# FrequencyGen.net
KiCad netlist of a schematic drawn in EAGLE
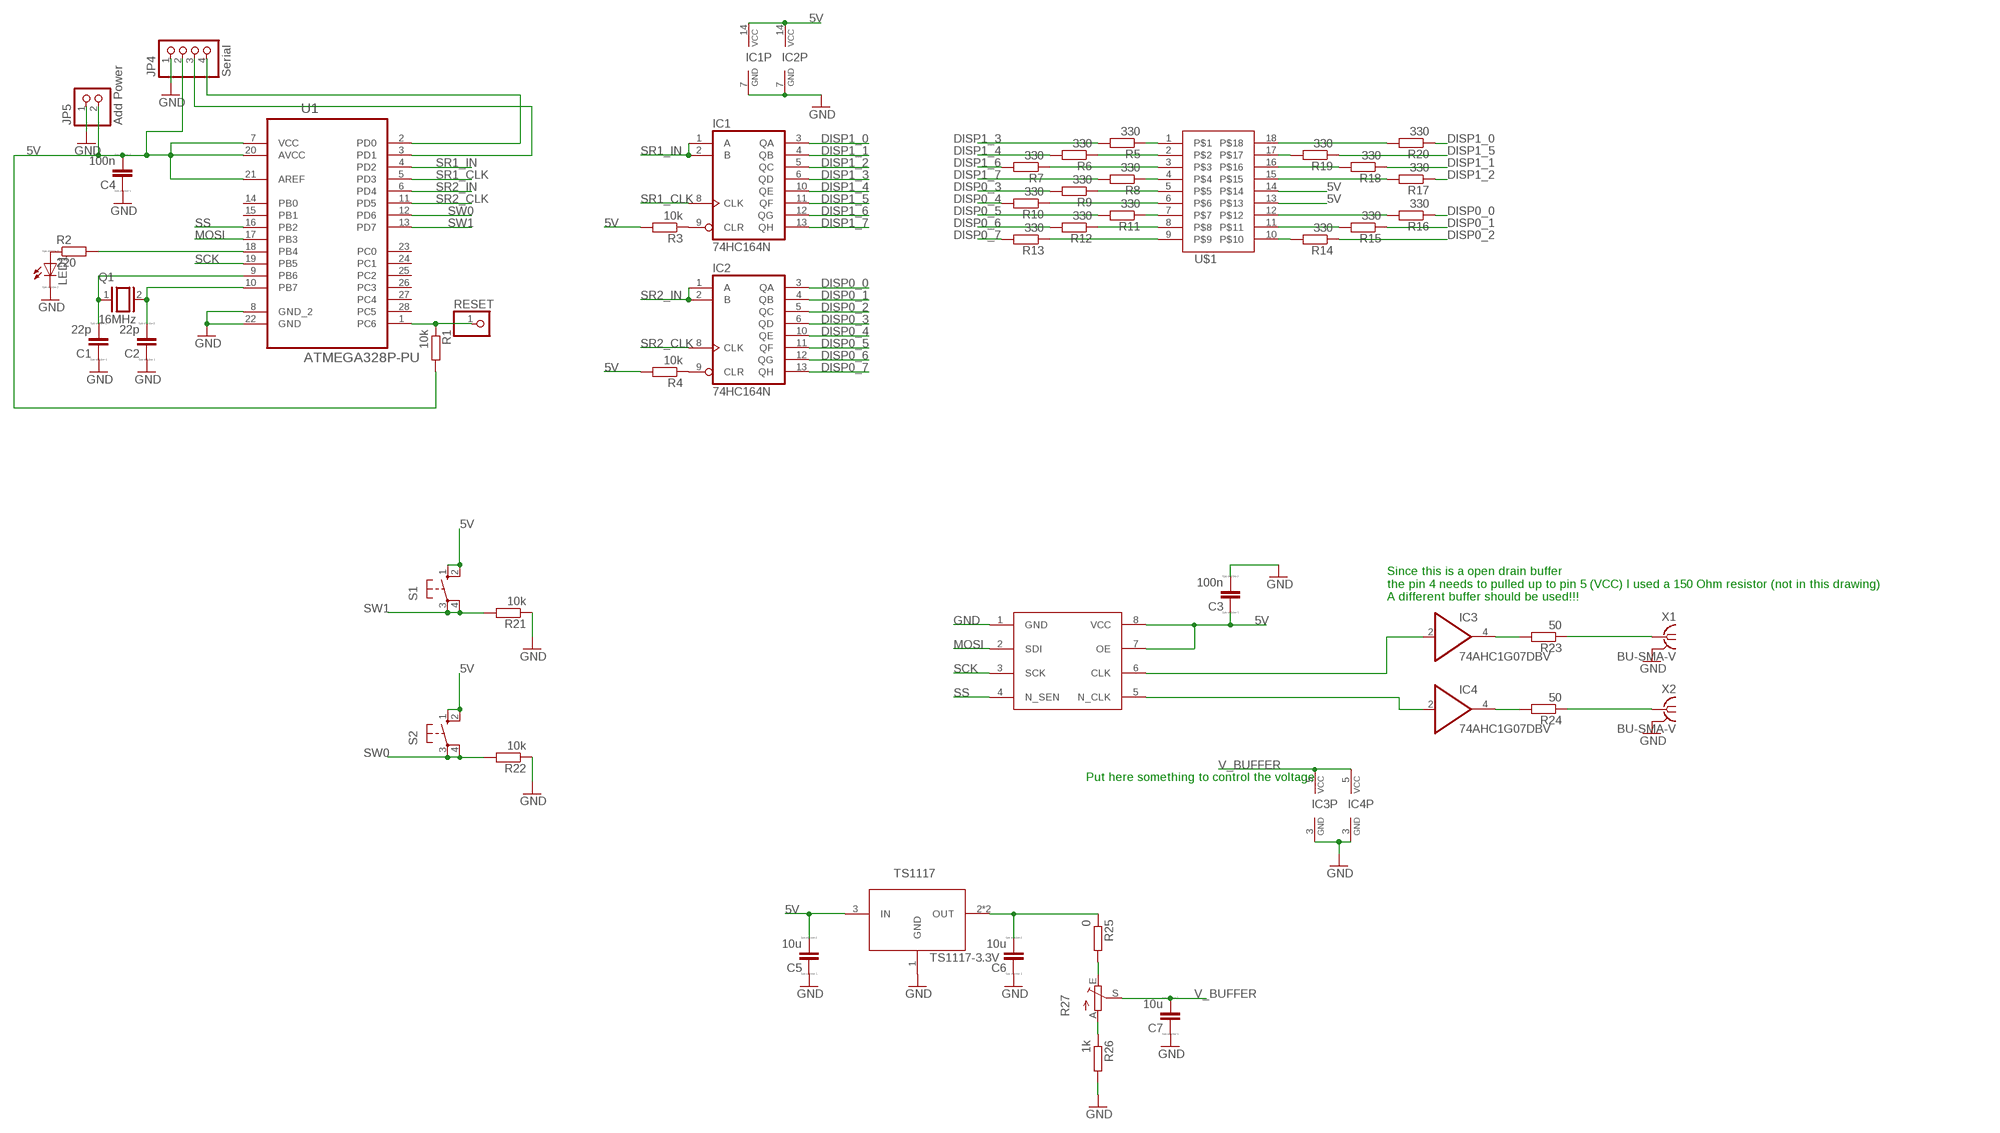
[diagram p0: schematic, sheet 1]

(export (version "E")
  (design (tool "Eeschema 10.0.6"))
  (components
    (comp (ref "C1")
      (value "22p")
      (footprint "eagle-import:C0805")
      (libsource (lib "eagle-import") (part "C_SMD"))
    )
    (comp (ref "C2")
      (value "22p")
      (footprint "eagle-import:C0805")
      (libsource (lib "eagle-import") (part "C_SMD"))
    )
    (comp (ref "C3")
      (value "100n")
      (footprint "eagle-import:C0805")
      (libsource (lib "eagle-import") (part "C_SMD"))
    )
    (comp (ref "C4")
      (value "100n")
      (footprint "eagle-import:C0805")
      (libsource (lib "eagle-import") (part "C_SMD"))
    )
    (comp (ref "C5")
      (value "10u")
      (footprint "eagle-import:C0805")
      (libsource (lib "eagle-import") (part "C_SMD"))
    )
    (comp (ref "C6")
      (value "10u")
      (footprint "eagle-import:C0805")
      (libsource (lib "eagle-import") (part "C_SMD"))
    )
    (comp (ref "C7")
      (value "10u")
      (footprint "eagle-import:C0805")
      (libsource (lib "eagle-import") (part "C_SMD"))
    )
    (comp (ref "IC1")
      (value "74HC164N")
      (footprint "eagle-import:DIL14")
      (libsource (lib "eagle-import") (part "74164NHC"))
    )
    (comp (ref "IC2")
      (value "74HC164N")
      (footprint "eagle-import:DIL14")
      (libsource (lib "eagle-import") (part "74164NHC"))
    )
    (comp (ref "IC3")
      (value "74AHC1G07DBV")
      (footprint "eagle-import:SOT23-5")
      (libsource (lib "eagle-import") (part "741G07DBVAHC"))
    )
    (comp (ref "IC4")
      (value "74AHC1G07DBV")
      (footprint "eagle-import:SOT23-5")
      (libsource (lib "eagle-import") (part "741G07DBVAHC"))
    )
    (comp (ref "JP4")
      (value "Serial")
      (footprint "eagle-import:1X04")
      (libsource (lib "eagle-import") (part "PINHD-1X4"))
    )
    (comp (ref "JP5")
      (value "Add Power")
      (footprint "eagle-import:1X02")
      (libsource (lib "eagle-import") (part "PINHD-1X2"))
    )
    (comp (ref "LED1")
      (value "LED_ELD260")
      (footprint "eagle-import:LED_LD260")
      (libsource (lib "eagle-import") (part "LED_ELD260"))
    )
    (comp (ref "Q1")
      (value "16MHz")
      (footprint "eagle-import:QS")
      (libsource (lib "eagle-import") (part "XTAL/S"))
    )
    (comp (ref "R1")
      (value "10k")
      (footprint "eagle-import:R0805")
      (libsource (lib "eagle-import") (part "R-EU_R0805"))
    )
    (comp (ref "R2")
      (value "220")
      (footprint "eagle-import:R0805")
      (libsource (lib "eagle-import") (part "R-EU_R0805"))
    )
    (comp (ref "R3")
      (value "10k")
      (footprint "eagle-import:R0805")
      (libsource (lib "eagle-import") (part "R-EU_R0805"))
    )
    (comp (ref "R4")
      (value "10k")
      (footprint "eagle-import:R0805")
      (libsource (lib "eagle-import") (part "R-EU_R0805"))
    )
    (comp (ref "R5")
      (value "330")
      (footprint "eagle-import:R0805")
      (libsource (lib "eagle-import") (part "R-EU_R0805"))
    )
    (comp (ref "R6")
      (value "330")
      (footprint "eagle-import:R0805")
      (libsource (lib "eagle-import") (part "R-EU_R0805"))
    )
    (comp (ref "R7")
      (value "330")
      (footprint "eagle-import:R0805")
      (libsource (lib "eagle-import") (part "R-EU_R0805"))
    )
    (comp (ref "R8")
      (value "330")
      (footprint "eagle-import:R0805")
      (libsource (lib "eagle-import") (part "R-EU_R0805"))
    )
    (comp (ref "R9")
      (value "330")
      (footprint "eagle-import:R0805")
      (libsource (lib "eagle-import") (part "R-EU_R0805"))
    )
    (comp (ref "R10")
      (value "330")
      (footprint "eagle-import:R0805")
      (libsource (lib "eagle-import") (part "R-EU_R0805"))
    )
    (comp (ref "R11")
      (value "330")
      (footprint "eagle-import:R0805")
      (libsource (lib "eagle-import") (part "R-EU_R0805"))
    )
    (comp (ref "R12")
      (value "330")
      (footprint "eagle-import:R0805")
      (libsource (lib "eagle-import") (part "R-EU_R0805"))
    )
    (comp (ref "R13")
      (value "330")
      (footprint "eagle-import:R0805")
      (libsource (lib "eagle-import") (part "R-EU_R0805"))
    )
    (comp (ref "R14")
      (value "330")
      (footprint "eagle-import:R0805")
      (libsource (lib "eagle-import") (part "R-EU_R0805"))
    )
    (comp (ref "R15")
      (value "330")
      (footprint "eagle-import:R0805")
      (libsource (lib "eagle-import") (part "R-EU_R0805"))
    )
    (comp (ref "R16")
      (value "330")
      (footprint "eagle-import:R0805")
      (libsource (lib "eagle-import") (part "R-EU_R0805"))
    )
    (comp (ref "R17")
      (value "330")
      (footprint "eagle-import:R0805")
      (libsource (lib "eagle-import") (part "R-EU_R0805"))
    )
    (comp (ref "R18")
      (value "330")
      (footprint "eagle-import:R0805")
      (libsource (lib "eagle-import") (part "R-EU_R0805"))
    )
    (comp (ref "R19")
      (value "330")
      (footprint "eagle-import:R0805")
      (libsource (lib "eagle-import") (part "R-EU_R0805"))
    )
    (comp (ref "R20")
      (value "330")
      (footprint "eagle-import:R0805")
      (libsource (lib "eagle-import") (part "R-EU_R0805"))
    )
    (comp (ref "R21")
      (value "10k")
      (footprint "eagle-import:R0805")
      (libsource (lib "eagle-import") (part "R-EU_R0805"))
    )
    (comp (ref "R22")
      (value "10k")
      (footprint "eagle-import:R0805")
      (libsource (lib "eagle-import") (part "R-EU_R0805"))
    )
    (comp (ref "R23")
      (value "50")
      (footprint "eagle-import:R0805")
      (libsource (lib "eagle-import") (part "R-EU_R0805"))
    )
    (comp (ref "R24")
      (value "50")
      (footprint "eagle-import:R0805")
      (libsource (lib "eagle-import") (part "R-EU_R0805"))
    )
    (comp (ref "R25")
      (value "0")
      (footprint "eagle-import:R0805")
      (libsource (lib "eagle-import") (part "R-EU_R0805"))
    )
    (comp (ref "R26")
      (value "1k")
      (footprint "eagle-import:R0805")
      (libsource (lib "eagle-import") (part "R-EU_R0805"))
    )
    (comp (ref "R27")
      (value "TRIM_EU-CA6V")
      (footprint "eagle-import:CA6V")
      (libsource (lib "eagle-import") (part "TRIM_EU-CA6V"))
    )
    (comp (ref "RESET")
      (value "PINHD-1X1")
      (footprint "eagle-import:1X01")
      (libsource (lib "eagle-import") (part "PINHD-1X1"))
    )
    (comp (ref "S1")
      (value "10-XX")
      (footprint "eagle-import:B3F-10XX")
      (fields (field (name "MPN") "B3F-1000"))
      (libsource (lib "eagle-import") (part "10-XX"))
    )
    (comp (ref "S2")
      (value "10-XX")
      (footprint "eagle-import:B3F-10XX")
      (fields (field (name "MPN") "B3F-1000"))
      (libsource (lib "eagle-import") (part "10-XX"))
    )
    (comp (ref "U$1")
      (value "SEG_DISP_2X8")
      (footprint "eagle-import:DIL18-6")
      (libsource (lib "eagle-import") (part "SEG_DISP_2X8"))
    )
    (comp (ref "U$2")
      (value "LTC6903")
      (footprint "eagle-import:MSOP8")
      (libsource (lib "eagle-import") (part "LTC6903"))
    )
    (comp (ref "U$3")
      (value "TS1117-3.3V")
      (footprint "eagle-import:SOT223")
      (libsource (lib "eagle-import") (part "TS1117"))
    )
    (comp (ref "U1")
      (value "ATMEGA328P-PU")
      (footprint "eagle-import:DIP254P762X457-28")
      (libsource (lib "eagle-import") (part "ATMEGA328P-PU"))
    )
    (comp (ref "X1")
      (value "BU-SMA-V")
      (footprint "eagle-import:BU-SMA-V")
      (libsource (lib "eagle-import") (part "BU-SMA-V"))
    )
    (comp (ref "X2")
      (value "BU-SMA-V")
      (footprint "eagle-import:BU-SMA-V")
      (libsource (lib "eagle-import") (part "BU-SMA-V"))
    )
  )
  (nets
    (net (code "1") (name "/5V") (class "Default")
      (node (ref "C3") (pin "1") (pinfunction "1_1") (pintype "passive"))
      (node (ref "C4") (pin "2") (pinfunction "2_2") (pintype "passive"))
      (node (ref "C5") (pin "2") (pinfunction "2_2") (pintype "passive"))
      (node (ref "IC1") (pin "14") (pinfunction "VCC_14") (pintype "power_in"))
      (node (ref "IC2") (pin "14") (pinfunction "VCC_14") (pintype "power_in"))
      (node (ref "JP4") (pin "2") (pinfunction "2_2") (pintype "passive"))
      (node (ref "JP5") (pin "2") (pinfunction "2_2") (pintype "passive"))
      (node (ref "R1") (pin "2") (pinfunction "2_2") (pintype "passive"))
      (node (ref "R3") (pin "2") (pinfunction "2_2") (pintype "passive"))
      (node (ref "R4") (pin "2") (pinfunction "2_2") (pintype "passive"))
      (node (ref "S1") (pin "1") (pinfunction "S_1") (pintype "passive"))
      (node (ref "S1") (pin "2") (pinfunction "S1_2") (pintype "passive"))
      (node (ref "S2") (pin "1") (pinfunction "S_1") (pintype "passive"))
      (node (ref "S2") (pin "2") (pinfunction "S1_2") (pintype "passive"))
      (node (ref "U$1") (pin "13") (pinfunction "P$13_13") (pintype "bidirectional"))
      (node (ref "U$1") (pin "14") (pinfunction "P$14_14") (pintype "bidirectional"))
      (node (ref "U$2") (pin "7") (pinfunction "OE_7") (pintype "bidirectional"))
      (node (ref "U$2") (pin "8") (pinfunction "VCC_8") (pintype "bidirectional"))
      (node (ref "U$3") (pin "3") (pinfunction "IN_3") (pintype "bidirectional"))
      (node (ref "U1") (pin "20") (pinfunction "AVCC_20") (pintype "power_in"))
      (node (ref "U1") (pin "21") (pinfunction "AREF_21") (pintype "input"))
      (node (ref "U1") (pin "7") (pinfunction "VCC_7") (pintype "power_in"))
    )
    (net (code "2") (name "/DISP0_0") (class "Default")
      (node (ref "IC2") (pin "3") (pinfunction "QA_3") (pintype "output"))
      (node (ref "R16") (pin "1") (pinfunction "1_1") (pintype "passive"))
    )
    (net (code "3") (name "/DISP0_1") (class "Default")
      (node (ref "IC2") (pin "4") (pinfunction "QB_4") (pintype "output"))
      (node (ref "R15") (pin "1") (pinfunction "1_1") (pintype "passive"))
    )
    (net (code "4") (name "/DISP0_2") (class "Default")
      (node (ref "IC2") (pin "5") (pinfunction "QC_5") (pintype "output"))
      (node (ref "R14") (pin "1") (pinfunction "1_1") (pintype "passive"))
    )
    (net (code "5") (name "/DISP0_3") (class "Default")
      (node (ref "IC2") (pin "6") (pinfunction "QD_6") (pintype "output"))
      (node (ref "R9") (pin "2") (pinfunction "2_2") (pintype "passive"))
    )
    (net (code "6") (name "/DISP0_4") (class "Default")
      (node (ref "IC2") (pin "10") (pinfunction "QE_10") (pintype "output"))
      (node (ref "R10") (pin "2") (pinfunction "2_2") (pintype "passive"))
    )
    (net (code "7") (name "/DISP0_5") (class "Default")
      (node (ref "IC2") (pin "11") (pinfunction "QF_11") (pintype "output"))
      (node (ref "R11") (pin "2") (pinfunction "2_2") (pintype "passive"))
    )
    (net (code "8") (name "/DISP0_6") (class "Default")
      (node (ref "IC2") (pin "12") (pinfunction "QG_12") (pintype "output"))
      (node (ref "R12") (pin "2") (pinfunction "2_2") (pintype "passive"))
    )
    (net (code "9") (name "/DISP0_7") (class "Default")
      (node (ref "IC2") (pin "13") (pinfunction "QH_13") (pintype "output"))
      (node (ref "R13") (pin "2") (pinfunction "2_2") (pintype "passive"))
    )
    (net (code "10") (name "/DISP1_0") (class "Default")
      (node (ref "IC1") (pin "3") (pinfunction "QA_3") (pintype "output"))
      (node (ref "R20") (pin "1") (pinfunction "1_1") (pintype "passive"))
    )
    (net (code "11") (name "/DISP1_1") (class "Default")
      (node (ref "IC1") (pin "4") (pinfunction "QB_4") (pintype "output"))
      (node (ref "R18") (pin "1") (pinfunction "1_1") (pintype "passive"))
    )
    (net (code "12") (name "/DISP1_2") (class "Default")
      (node (ref "IC1") (pin "5") (pinfunction "QC_5") (pintype "output"))
      (node (ref "R17") (pin "1") (pinfunction "1_1") (pintype "passive"))
    )
    (net (code "13") (name "/DISP1_3") (class "Default")
      (node (ref "IC1") (pin "6") (pinfunction "QD_6") (pintype "output"))
      (node (ref "R5") (pin "2") (pinfunction "2_2") (pintype "passive"))
    )
    (net (code "14") (name "/DISP1_4") (class "Default")
      (node (ref "IC1") (pin "10") (pinfunction "QE_10") (pintype "output"))
      (node (ref "R6") (pin "2") (pinfunction "2_2") (pintype "passive"))
    )
    (net (code "15") (name "/DISP1_5") (class "Default")
      (node (ref "IC1") (pin "11") (pinfunction "QF_11") (pintype "output"))
      (node (ref "R19") (pin "1") (pinfunction "1_1") (pintype "passive"))
    )
    (net (code "16") (name "/DISP1_6") (class "Default")
      (node (ref "IC1") (pin "12") (pinfunction "QG_12") (pintype "output"))
      (node (ref "R7") (pin "2") (pinfunction "2_2") (pintype "passive"))
    )
    (net (code "17") (name "/DISP1_7") (class "Default")
      (node (ref "IC1") (pin "13") (pinfunction "QH_13") (pintype "output"))
      (node (ref "R8") (pin "2") (pinfunction "2_2") (pintype "passive"))
    )
    (net (code "18") (name "/MOSI") (class "Default")
      (node (ref "U$2") (pin "2") (pinfunction "SDI_2") (pintype "bidirectional"))
      (node (ref "U1") (pin "17") (pinfunction "PB3_17") (pintype "bidirectional"))
    )
    (net (code "19") (name "/SCK") (class "Default")
      (node (ref "U$2") (pin "3") (pinfunction "SCK_3") (pintype "bidirectional"))
      (node (ref "U1") (pin "19") (pinfunction "PB5_19") (pintype "bidirectional"))
    )
    (net (code "20") (name "/SR1_CLK") (class "Default")
      (node (ref "IC1") (pin "8") (pinfunction "CLK_8") (pintype "input"))
      (node (ref "U1") (pin "5") (pinfunction "PD3_5") (pintype "bidirectional"))
    )
    (net (code "21") (name "/SR1_IN") (class "Default")
      (node (ref "IC1") (pin "1") (pinfunction "A_1") (pintype "input"))
      (node (ref "IC1") (pin "2") (pinfunction "B_2") (pintype "input"))
      (node (ref "U1") (pin "4") (pinfunction "PD2_4") (pintype "bidirectional"))
    )
    (net (code "22") (name "/SR2_CLK") (class "Default")
      (node (ref "IC2") (pin "8") (pinfunction "CLK_8") (pintype "input"))
      (node (ref "U1") (pin "11") (pinfunction "PD5_11") (pintype "bidirectional"))
    )
    (net (code "23") (name "/SR2_IN") (class "Default")
      (node (ref "IC2") (pin "1") (pinfunction "A_1") (pintype "input"))
      (node (ref "IC2") (pin "2") (pinfunction "B_2") (pintype "input"))
      (node (ref "U1") (pin "6") (pinfunction "PD4_6") (pintype "bidirectional"))
    )
    (net (code "24") (name "/SS") (class "Default")
      (node (ref "U$2") (pin "4") (pinfunction "N_SEN_4") (pintype "bidirectional"))
      (node (ref "U1") (pin "16") (pinfunction "PB2_16") (pintype "bidirectional"))
    )
    (net (code "25") (name "/SW0") (class "Default")
      (node (ref "R22") (pin "2") (pinfunction "2_2") (pintype "passive"))
      (node (ref "S2") (pin "3") (pinfunction "P_3") (pintype "passive"))
      (node (ref "S2") (pin "4") (pinfunction "P1_4") (pintype "passive"))
      (node (ref "U1") (pin "12") (pinfunction "PD6_12") (pintype "bidirectional"))
    )
    (net (code "26") (name "/SW1") (class "Default")
      (node (ref "R21") (pin "2") (pinfunction "2_2") (pintype "passive"))
      (node (ref "S1") (pin "3") (pinfunction "P_3") (pintype "passive"))
      (node (ref "S1") (pin "4") (pinfunction "P1_4") (pintype "passive"))
      (node (ref "U1") (pin "13") (pinfunction "PD7_13") (pintype "bidirectional"))
    )
    (net (code "27") (name "/V_BUFFER") (class "Default")
      (node (ref "C7") (pin "2") (pinfunction "2_2") (pintype "passive"))
      (node (ref "IC3") (pin "5") (pinfunction "VCC_5") (pintype "power_in"))
      (node (ref "IC4") (pin "5") (pinfunction "VCC_5") (pintype "power_in"))
      (node (ref "R27") (pin "S") (pinfunction "S_S") (pintype "passive"))
    )
    (net (code "28") (name "GND") (class "Default")
      (node (ref "C1") (pin "1") (pinfunction "1_1") (pintype "passive"))
      (node (ref "C2") (pin "1") (pinfunction "1_1") (pintype "passive"))
      (node (ref "C3") (pin "2") (pinfunction "2_2") (pintype "passive"))
      (node (ref "C4") (pin "1") (pinfunction "1_1") (pintype "passive"))
      (node (ref "C5") (pin "1") (pinfunction "1_1") (pintype "passive"))
      (node (ref "C6") (pin "1") (pinfunction "1_1") (pintype "passive"))
      (node (ref "C7") (pin "1") (pinfunction "1_1") (pintype "passive"))
      (node (ref "IC1") (pin "7") (pinfunction "GND_7") (pintype "power_in"))
      (node (ref "IC2") (pin "7") (pinfunction "GND_7") (pintype "power_in"))
      (node (ref "IC3") (pin "3") (pinfunction "GND_3") (pintype "power_in"))
      (node (ref "IC4") (pin "3") (pinfunction "GND_3") (pintype "power_in"))
      (node (ref "JP4") (pin "1") (pinfunction "1_1") (pintype "passive"))
      (node (ref "JP5") (pin "1") (pinfunction "1_1") (pintype "passive"))
      (node (ref "LED1") (pin "K") (pinfunction "C_K") (pintype "passive"))
      (node (ref "R21") (pin "1") (pinfunction "1_1") (pintype "passive"))
      (node (ref "R22") (pin "1") (pinfunction "1_1") (pintype "passive"))
      (node (ref "R26") (pin "2") (pinfunction "2_2") (pintype "passive"))
      (node (ref "U$2") (pin "1") (pinfunction "GND_1") (pintype "bidirectional"))
      (node (ref "U$3") (pin "1") (pinfunction "GND_1") (pintype "bidirectional"))
      (node (ref "U1") (pin "22") (pinfunction "GND_22") (pintype "passive"))
      (node (ref "U1") (pin "8") (pinfunction "GND_2_8") (pintype "passive"))
      (node (ref "X1") (pin "2") (pinfunction "2_2") (pintype "passive"))
      (node (ref "X1") (pin "3") (pinfunction "2_3") (pintype "passive"))
      (node (ref "X1") (pin "4") (pinfunction "2_4") (pintype "passive"))
      (node (ref "X1") (pin "5") (pinfunction "2_5") (pintype "passive"))
      (node (ref "X2") (pin "2") (pinfunction "2_2") (pintype "passive"))
      (node (ref "X2") (pin "3") (pinfunction "2_3") (pintype "passive"))
      (node (ref "X2") (pin "4") (pinfunction "2_4") (pintype "passive"))
      (node (ref "X2") (pin "5") (pinfunction "2_5") (pintype "passive"))
    )
    (net (code "29") (name "Net-(C6-Pad2)") (class "Default")
      (node (ref "C6") (pin "2") (pinfunction "2_2") (pintype "passive"))
      (node (ref "R25") (pin "1") (pinfunction "1_1") (pintype "passive"))
      (node (ref "U$3") (pin "2") (pinfunction "OUT_2") (pintype "bidirectional"))
      (node (ref "U$3") (pin "4") (pinfunction "OUT_4") (pintype "bidirectional"))
    )
    (net (code "30") (name "Net-(IC1A-CLR)") (class "Default")
      (node (ref "IC1") (pin "9") (pinfunction "CLR_9") (pintype "input"))
      (node (ref "R3") (pin "1") (pinfunction "1_1") (pintype "passive"))
    )
    (net (code "31") (name "Net-(IC2A-CLR)") (class "Default")
      (node (ref "IC2") (pin "9") (pinfunction "CLR_9") (pintype "input"))
      (node (ref "R4") (pin "1") (pinfunction "1_1") (pintype "passive"))
    )
    (net (code "32") (name "Net-(IC3A-I)") (class "Default")
      (node (ref "IC3") (pin "2") (pinfunction "I_2") (pintype "input"))
      (node (ref "U$2") (pin "6") (pinfunction "CLK_6") (pintype "bidirectional"))
    )
    (net (code "33") (name "Net-(IC3A-O)") (class "Default")
      (node (ref "IC3") (pin "4") (pinfunction "O_4") (pintype "open_collector"))
      (node (ref "R23") (pin "2") (pinfunction "2_2") (pintype "passive"))
    )
    (net (code "34") (name "Net-(IC4A-I)") (class "Default")
      (node (ref "IC4") (pin "2") (pinfunction "I_2") (pintype "input"))
      (node (ref "U$2") (pin "5") (pinfunction "N_CLK_5") (pintype "bidirectional"))
    )
    (net (code "35") (name "Net-(IC4A-O)") (class "Default")
      (node (ref "IC4") (pin "4") (pinfunction "O_4") (pintype "open_collector"))
      (node (ref "R24") (pin "2") (pinfunction "2_2") (pintype "passive"))
    )
    (net (code "36") (name "Net-(LED1-PadA)") (class "Default")
      (node (ref "LED1") (pin "A") (pinfunction "A_A") (pintype "passive"))
      (node (ref "R2") (pin "1") (pinfunction "1_1") (pintype "passive"))
    )
    (net (code "37") (name "Net-(R23-Pad1)") (class "Default")
      (node (ref "R23") (pin "1") (pinfunction "1_1") (pintype "passive"))
      (node (ref "X1") (pin "1") (pinfunction "1_1") (pintype "passive"))
    )
    (net (code "38") (name "Net-(R24-Pad1)") (class "Default")
      (node (ref "R24") (pin "1") (pinfunction "1_1") (pintype "passive"))
      (node (ref "X2") (pin "1") (pinfunction "1_1") (pintype "passive"))
    )
    (net (code "39") (name "Net-(R25-Pad2)") (class "Default")
      (node (ref "R25") (pin "2") (pinfunction "2_2") (pintype "passive"))
      (node (ref "R27") (pin "E") (pinfunction "E_E") (pintype "passive"))
    )
    (net (code "40") (name "Net-(R26-Pad1)") (class "Default")
      (node (ref "R26") (pin "1") (pinfunction "1_1") (pintype "passive"))
      (node (ref "R27") (pin "A") (pinfunction "A_A") (pintype "passive"))
    )
    (net (code "41") (name "Net-(U$1-P$1)") (class "Default")
      (node (ref "R5") (pin "1") (pinfunction "1_1") (pintype "passive"))
      (node (ref "U$1") (pin "1") (pinfunction "P$1_1") (pintype "bidirectional"))
    )
    (net (code "42") (name "Net-(U$1-P$2)") (class "Default")
      (node (ref "R6") (pin "1") (pinfunction "1_1") (pintype "passive"))
      (node (ref "U$1") (pin "2") (pinfunction "P$2_2") (pintype "bidirectional"))
    )
    (net (code "43") (name "Net-(U$1-P$3)") (class "Default")
      (node (ref "R7") (pin "1") (pinfunction "1_1") (pintype "passive"))
      (node (ref "U$1") (pin "3") (pinfunction "P$3_3") (pintype "bidirectional"))
    )
    (net (code "44") (name "Net-(U$1-P$4)") (class "Default")
      (node (ref "R8") (pin "1") (pinfunction "1_1") (pintype "passive"))
      (node (ref "U$1") (pin "4") (pinfunction "P$4_4") (pintype "bidirectional"))
    )
    (net (code "45") (name "Net-(U$1-P$5)") (class "Default")
      (node (ref "R9") (pin "1") (pinfunction "1_1") (pintype "passive"))
      (node (ref "U$1") (pin "5") (pinfunction "P$5_5") (pintype "bidirectional"))
    )
    (net (code "46") (name "Net-(U$1-P$6)") (class "Default")
      (node (ref "R10") (pin "1") (pinfunction "1_1") (pintype "passive"))
      (node (ref "U$1") (pin "6") (pinfunction "P$6_6") (pintype "bidirectional"))
    )
    (net (code "47") (name "Net-(U$1-P$7)") (class "Default")
      (node (ref "R11") (pin "1") (pinfunction "1_1") (pintype "passive"))
      (node (ref "U$1") (pin "7") (pinfunction "P$7_7") (pintype "bidirectional"))
    )
    (net (code "48") (name "Net-(U$1-P$8)") (class "Default")
      (node (ref "R12") (pin "1") (pinfunction "1_1") (pintype "passive"))
      (node (ref "U$1") (pin "8") (pinfunction "P$8_8") (pintype "bidirectional"))
    )
    (net (code "49") (name "Net-(U$1-P$9)") (class "Default")
      (node (ref "R13") (pin "1") (pinfunction "1_1") (pintype "passive"))
      (node (ref "U$1") (pin "9") (pinfunction "P$9_9") (pintype "bidirectional"))
    )
    (net (code "50") (name "Net-(U$1-P$10)") (class "Default")
      (node (ref "R14") (pin "2") (pinfunction "2_2") (pintype "passive"))
      (node (ref "U$1") (pin "10") (pinfunction "P$10_10") (pintype "bidirectional"))
    )
    (net (code "51") (name "Net-(U$1-P$11)") (class "Default")
      (node (ref "R15") (pin "2") (pinfunction "2_2") (pintype "passive"))
      (node (ref "U$1") (pin "11") (pinfunction "P$11_11") (pintype "bidirectional"))
    )
    (net (code "52") (name "Net-(U$1-P$12)") (class "Default")
      (node (ref "R16") (pin "2") (pinfunction "2_2") (pintype "passive"))
      (node (ref "U$1") (pin "12") (pinfunction "P$12_12") (pintype "bidirectional"))
    )
    (net (code "53") (name "Net-(U$1-P$15)") (class "Default")
      (node (ref "R17") (pin "2") (pinfunction "2_2") (pintype "passive"))
      (node (ref "U$1") (pin "15") (pinfunction "P$15_15") (pintype "bidirectional"))
    )
    (net (code "54") (name "Net-(U$1-P$16)") (class "Default")
      (node (ref "R18") (pin "2") (pinfunction "2_2") (pintype "passive"))
      (node (ref "U$1") (pin "16") (pinfunction "P$16_16") (pintype "bidirectional"))
    )
    (net (code "55") (name "Net-(U$1-P$17)") (class "Default")
      (node (ref "R19") (pin "2") (pinfunction "2_2") (pintype "passive"))
      (node (ref "U$1") (pin "17") (pinfunction "P$17_17") (pintype "bidirectional"))
    )
    (net (code "56") (name "Net-(U$1-P$18)") (class "Default")
      (node (ref "R20") (pin "2") (pinfunction "2_2") (pintype "passive"))
      (node (ref "U$1") (pin "18") (pinfunction "P$18_18") (pintype "bidirectional"))
    )
    (net (code "57") (name "Net-(U1-PB4)") (class "Default")
      (node (ref "R2") (pin "2") (pinfunction "2_2") (pintype "passive"))
      (node (ref "U1") (pin "18") (pinfunction "PB4_18") (pintype "bidirectional"))
    )
    (net (code "58") (name "Net-(U1-PB6)") (class "Default")
      (node (ref "C1") (pin "2") (pinfunction "2_2") (pintype "passive"))
      (node (ref "Q1") (pin "1") (pinfunction "1_1") (pintype "passive"))
      (node (ref "U1") (pin "9") (pinfunction "PB6_9") (pintype "bidirectional"))
    )
    (net (code "59") (name "Net-(U1-PB7)") (class "Default")
      (node (ref "C2") (pin "2") (pinfunction "2_2") (pintype "passive"))
      (node (ref "Q1") (pin "2") (pinfunction "2_2") (pintype "passive"))
      (node (ref "U1") (pin "10") (pinfunction "PB7_10") (pintype "bidirectional"))
    )
    (net (code "60") (name "Net-(U1-PC6)") (class "Default")
      (node (ref "R1") (pin "1") (pinfunction "1_1") (pintype "passive"))
      (node (ref "RESET") (pin "1") (pinfunction "1_1") (pintype "passive"))
      (node (ref "U1") (pin "1") (pinfunction "PC6_1") (pintype "bidirectional"))
    )
    (net (code "61") (name "Net-(U1-PD0)") (class "Default")
      (node (ref "JP4") (pin "4") (pinfunction "4_4") (pintype "passive"))
      (node (ref "U1") (pin "2") (pinfunction "PD0_2") (pintype "bidirectional"))
    )
    (net (code "62") (name "Net-(U1-PD1)") (class "Default")
      (node (ref "JP4") (pin "3") (pinfunction "3_3") (pintype "passive"))
      (node (ref "U1") (pin "3") (pinfunction "PD1_3") (pintype "bidirectional"))
    )
    (net (code "63") (name "unconnected-(U1-PB0-Pad14)") (class "Default")
      (node (ref "U1") (pin "14") (pinfunction "PB0_14") (pintype "bidirectional"))
    )
    (net (code "64") (name "unconnected-(U1-PB1-Pad15)") (class "Default")
      (node (ref "U1") (pin "15") (pinfunction "PB1_15") (pintype "bidirectional"))
    )
    (net (code "65") (name "unconnected-(U1-PC0-Pad23)") (class "Default")
      (node (ref "U1") (pin "23") (pinfunction "PC0_23") (pintype "bidirectional"))
    )
    (net (code "66") (name "unconnected-(U1-PC1-Pad24)") (class "Default")
      (node (ref "U1") (pin "24") (pinfunction "PC1_24") (pintype "bidirectional"))
    )
    (net (code "67") (name "unconnected-(U1-PC2-Pad25)") (class "Default")
      (node (ref "U1") (pin "25") (pinfunction "PC2_25") (pintype "bidirectional"))
    )
    (net (code "68") (name "unconnected-(U1-PC3-Pad26)") (class "Default")
      (node (ref "U1") (pin "26") (pinfunction "PC3_26") (pintype "bidirectional"))
    )
    (net (code "69") (name "unconnected-(U1-PC4-Pad27)") (class "Default")
      (node (ref "U1") (pin "27") (pinfunction "PC4_27") (pintype "bidirectional"))
    )
    (net (code "70") (name "unconnected-(U1-PC5-Pad28)") (class "Default")
      (node (ref "U1") (pin "28") (pinfunction "PC5_28") (pintype "bidirectional"))
    )
  )
)
